# MCU_and_Acc.net
KiCad netlist of a schematic drawn in Altium Designer
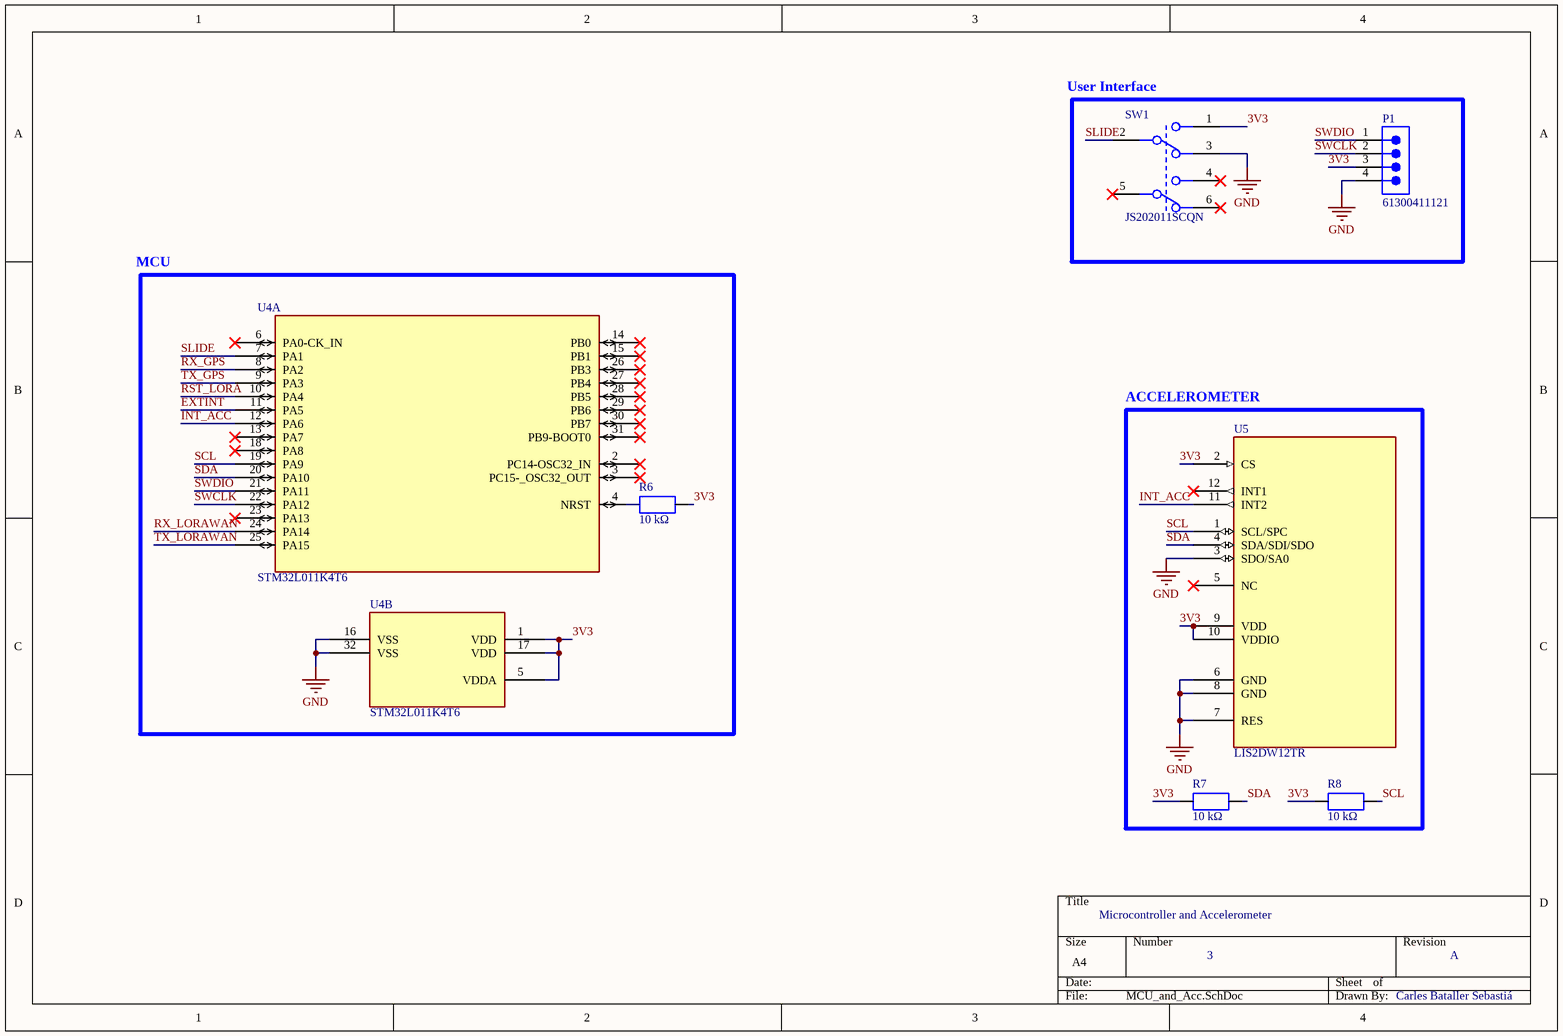
[diagram p0: MCU_and_Acc.SchDoc]

(export (version "E")
  (design (tool "Eeschema 10.0.6"))
  (components
    (comp (ref "P1")
      (value "61300411121")
      (footprint "61300411121")
      (description "THT Vertical Pin Header WR-PHD, Pitch 2.54 mm, Single Row, 4 pins")
      (libsource (lib "Generic-Schematic-Library") (part "CMP-1502-01064-4"))
    )
    (comp (ref "R6")
      (value "10 kΩ")
      (footprint "RES_0201")
      (description "Thick Film Resistors - SMD 0201 10K0 1% Lead Free")
      (fields (field (name "TOLERANCE") "0.1%") (field (name "LCSC PART NUMBER") "C852221"))
      (libsource (lib "Generic-Schematic-Library") (part "RES_0201"))
    )
    (comp (ref "R7")
      (value "10 kΩ")
      (footprint "RES_0201")
      (description "Thick Film Resistors - SMD 0201 10K0 1% Lead Free")
      (fields (field (name "TOLERANCE") "0.1%") (field (name "LCSC PART NUMBER") "C852221"))
      (libsource (lib "Generic-Schematic-Library") (part "RES_0201"))
    )
    (comp (ref "R8")
      (value "10 kΩ")
      (footprint "RES_0201")
      (description "Thick Film Resistors - SMD 0201 10K0 1% Lead Free")
      (fields (field (name "TOLERANCE") "0.1%") (field (name "LCSC PART NUMBER") "C852221"))
      (libsource (lib "Generic-Schematic-Library") (part "RES_0201"))
    )
    (comp (ref "SW1")
      (value "JS202011SCQN")
      (footprint "FP-JS202011SCQN-MFG")
      (description "SWITCH SLIDE DPDT 300MA 6V")
      (libsource (lib "Generic-Schematic-Library") (part "CMP-2000-05087-3"))
    )
    (comp (ref "U4")
      (value "STM32L011K4T6")
      (footprint "LQFP32_7X7X1P4")
      (description "Ultra-low-power Arm Cortex-M0+ MCU with 16-Kbytes of Flash memory, 32 MHz CPU")
      (fields (field (name "COPYRIGHT") "Copyright (C) 2026 Ultra Librarian. All rights reserved."))
      (libsource (lib "Generic-Schematic-Library") (part "STM32L011K4T6"))
    )
    (comp (ref "U5")
      (value "LIS2DW12TR")
      (footprint "LGA-12_2X2X0P7_STM")
      (fields (field (name "COPYRIGHT") "Copyright (C) 2026 Ultra Librarian. All rights reserved."))
      (libsource (lib "Generic-Schematic-Library") (part "LIS2DW12TR"))
    )
  )
  (nets
    (net (code "1") (name "/3V3") (class "Default")
      (node (ref "P1") (pin "3") (pinfunction "3_3") (pintype "passive"))
      (node (ref "R6") (pin "1") (pinfunction "1_1") (pintype "passive"))
      (node (ref "R7") (pin "2") (pinfunction "2_2") (pintype "passive"))
      (node (ref "R8") (pin "2") (pinfunction "2_2") (pintype "passive"))
      (node (ref "SW1") (pin "1") (pinfunction "1_1") (pintype "passive"))
      (node (ref "U4") (pin "1") (pinfunction "VDD_1") (pintype "power_in"))
      (node (ref "U4") (pin "17") (pinfunction "VDD_17") (pintype "power_in"))
      (node (ref "U4") (pin "5") (pinfunction "VDDA_5") (pintype "power_in"))
      (node (ref "U5") (pin "10") (pinfunction "VDDIO_10") (pintype "power_in"))
      (node (ref "U5") (pin "2") (pinfunction "CS_2") (pintype "input"))
      (node (ref "U5") (pin "9") (pinfunction "VDD_9") (pintype "power_in"))
    )
    (net (code "2") (name "/EXTINT") (class "Default")
      (node (ref "U4") (pin "11") (pinfunction "PA5_11") (pintype "passive"))
    )
    (net (code "3") (name "/INT_ACC") (class "Default")
      (node (ref "U4") (pin "12") (pinfunction "PA6_12") (pintype "passive"))
      (node (ref "U5") (pin "11") (pinfunction "INT2_11") (pintype "output"))
    )
    (net (code "4") (name "/RST_LORA") (class "Default")
      (node (ref "U4") (pin "10") (pinfunction "PA4_10") (pintype "passive"))
    )
    (net (code "5") (name "/RX_GPS") (class "Default")
      (node (ref "U4") (pin "8") (pinfunction "PA2_8") (pintype "passive"))
    )
    (net (code "6") (name "/RX_LORAWAN") (class "Default")
      (node (ref "U4") (pin "24") (pinfunction "PA14_24") (pintype "passive"))
    )
    (net (code "7") (name "/SCL") (class "Default")
      (node (ref "R8") (pin "1") (pinfunction "1_1") (pintype "passive"))
      (node (ref "U4") (pin "19") (pinfunction "PA9_19") (pintype "passive"))
      (node (ref "U5") (pin "1") (pinfunction "SCL/SPC_1") (pintype "bidirectional"))
    )
    (net (code "8") (name "/SDA") (class "Default")
      (node (ref "R7") (pin "1") (pinfunction "1_1") (pintype "passive"))
      (node (ref "U4") (pin "20") (pinfunction "PA10_20") (pintype "passive"))
      (node (ref "U5") (pin "4") (pinfunction "SDA/SDI/SDO_4") (pintype "bidirectional"))
    )
    (net (code "9") (name "/SLIDE") (class "Default")
      (node (ref "SW1") (pin "2") (pinfunction "2_2") (pintype "passive"))
      (node (ref "U4") (pin "7") (pinfunction "PA1_7") (pintype "passive"))
    )
    (net (code "10") (name "/SWCLK") (class "Default")
      (node (ref "P1") (pin "2") (pinfunction "2_2") (pintype "passive"))
      (node (ref "U4") (pin "22") (pinfunction "PA12_22") (pintype "passive"))
    )
    (net (code "11") (name "/SWDIO") (class "Default")
      (node (ref "P1") (pin "1") (pinfunction "1_1") (pintype "passive"))
      (node (ref "U4") (pin "21") (pinfunction "PA11_21") (pintype "passive"))
    )
    (net (code "12") (name "/TX_GPS") (class "Default")
      (node (ref "U4") (pin "9") (pinfunction "PA3_9") (pintype "passive"))
    )
    (net (code "13") (name "/TX_LORAWAN") (class "Default")
      (node (ref "U4") (pin "25") (pinfunction "PA15_25") (pintype "passive"))
    )
    (net (code "14") (name "GND") (class "Default")
      (node (ref "P1") (pin "4") (pinfunction "4_4") (pintype "passive"))
      (node (ref "SW1") (pin "3") (pinfunction "3_3") (pintype "passive"))
      (node (ref "U4") (pin "16") (pinfunction "VSS_16") (pintype "power_in"))
      (node (ref "U4") (pin "32") (pinfunction "VSS_32") (pintype "power_in"))
      (node (ref "U5") (pin "3") (pinfunction "SDO/SA0_3") (pintype "bidirectional"))
      (node (ref "U5") (pin "6") (pinfunction "GND_6") (pintype "power_in"))
      (node (ref "U5") (pin "7") (pinfunction "RES_7") (pintype "power_in"))
      (node (ref "U5") (pin "8") (pinfunction "GND_8") (pintype "power_in"))
    )
    (net (code "15") (name "Net-(U4A-NRST)") (class "Default")
      (node (ref "R6") (pin "2") (pinfunction "2_2") (pintype "passive"))
      (node (ref "U4") (pin "4") (pinfunction "NRST_4") (pintype "passive"))
    )
    (net (code "16") (name "unconnected-(SW1-Pad4)") (class "Default")
      (node (ref "SW1") (pin "4") (pinfunction "4_4") (pintype "passive+no_connect"))
    )
    (net (code "17") (name "unconnected-(SW1-Pad5)") (class "Default")
      (node (ref "SW1") (pin "5") (pinfunction "5_5") (pintype "passive+no_connect"))
    )
    (net (code "18") (name "unconnected-(SW1-Pad6)") (class "Default")
      (node (ref "SW1") (pin "6") (pinfunction "6_6") (pintype "passive+no_connect"))
    )
    (net (code "19") (name "unconnected-(U4A-PA0-CK_IN-Pad6)") (class "Default")
      (node (ref "U4") (pin "6") (pinfunction "PA0-CK_IN_6") (pintype "passive+no_connect"))
    )
    (net (code "20") (name "unconnected-(U4A-PA7-Pad13)") (class "Default")
      (node (ref "U4") (pin "13") (pinfunction "PA7_13") (pintype "passive+no_connect"))
    )
    (net (code "21") (name "unconnected-(U4A-PA8-Pad18)") (class "Default")
      (node (ref "U4") (pin "18") (pinfunction "PA8_18") (pintype "passive+no_connect"))
    )
    (net (code "22") (name "unconnected-(U4A-PA13-Pad23)") (class "Default")
      (node (ref "U4") (pin "23") (pinfunction "PA13_23") (pintype "passive+no_connect"))
    )
    (net (code "23") (name "unconnected-(U4A-PB0-Pad14)") (class "Default")
      (node (ref "U4") (pin "14") (pinfunction "PB0_14") (pintype "passive+no_connect"))
    )
    (net (code "24") (name "unconnected-(U4A-PB1-Pad15)") (class "Default")
      (node (ref "U4") (pin "15") (pinfunction "PB1_15") (pintype "passive+no_connect"))
    )
    (net (code "25") (name "unconnected-(U4A-PB3-Pad26)") (class "Default")
      (node (ref "U4") (pin "26") (pinfunction "PB3_26") (pintype "passive+no_connect"))
    )
    (net (code "26") (name "unconnected-(U4A-PB4-Pad27)") (class "Default")
      (node (ref "U4") (pin "27") (pinfunction "PB4_27") (pintype "passive+no_connect"))
    )
    (net (code "27") (name "unconnected-(U4A-PB5-Pad28)") (class "Default")
      (node (ref "U4") (pin "28") (pinfunction "PB5_28") (pintype "passive+no_connect"))
    )
    (net (code "28") (name "unconnected-(U4A-PB6-Pad29)") (class "Default")
      (node (ref "U4") (pin "29") (pinfunction "PB6_29") (pintype "passive+no_connect"))
    )
    (net (code "29") (name "unconnected-(U4A-PB7-Pad30)") (class "Default")
      (node (ref "U4") (pin "30") (pinfunction "PB7_30") (pintype "passive+no_connect"))
    )
    (net (code "30") (name "unconnected-(U4A-PB9-BOOT0-Pad31)") (class "Default")
      (node (ref "U4") (pin "31") (pinfunction "PB9-BOOT0_31") (pintype "passive+no_connect"))
    )
    (net (code "31") (name "unconnected-(U4A-PC14-OSC32_IN-Pad2)") (class "Default")
      (node (ref "U4") (pin "2") (pinfunction "PC14-OSC32_IN_2") (pintype "passive+no_connect"))
    )
    (net (code "32") (name "unconnected-(U4A-PC15-_OSC32_OUT-Pad3)") (class "Default")
      (node (ref "U4") (pin "3") (pinfunction "PC15-_OSC32_OUT_3") (pintype "passive+no_connect"))
    )
    (net (code "33") (name "unconnected-(U5-INT1-Pad12)") (class "Default")
      (node (ref "U5") (pin "12") (pinfunction "INT1_12") (pintype "output+no_connect"))
    )
    (net (code "34") (name "unconnected-(U5-NC-Pad5)") (class "Default")
      (node (ref "U5") (pin "5") (pinfunction "NC_5") (pintype "passive+no_connect"))
    )
  )
)
